# relais_platine_v2.net
KiCad netlist of a schematic drawn in EAGLE
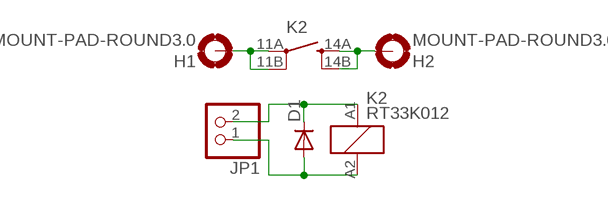
[diagram p0: schematic, sheet 1]

(export (version "E")
  (design (tool "Eeschema 10.0.6"))
  (components
    (comp (ref "D1")
      (value "DIODE-D-5")
      (footprint "eagle-import:D-5")
      (libsource (lib "eagle-import") (part "DIODE-D-5"))
    )
    (comp (ref "H1")
      (value "MOUNT-PAD-ROUND3.0")
      (footprint "eagle-import:3,0-PAD")
      (libsource (lib "eagle-import") (part "MOUNT-PAD-ROUND3.0"))
    )
    (comp (ref "H2")
      (value "MOUNT-PAD-ROUND3.0")
      (footprint "eagle-import:3,0-PAD")
      (libsource (lib "eagle-import") (part "MOUNT-PAD-ROUND3.0"))
    )
    (comp (ref "JP1")
      (value "PINHD-1X2")
      (footprint "eagle-import:1X02")
      (libsource (lib "eagle-import") (part "PINHD-1X2"))
    )
    (comp (ref "K2")
      (value "RT33K012")
      (footprint "eagle-import:RT-N_O16A5")
      (libsource (lib "eagle-import") (part "RT33K012"))
    )
  )
  (nets
    (net (code "1") (name "Net-(H1-MOUNT)") (class "Default")
      (node (ref "H1") (pin "B3,0") (pinfunction "MOUNT_B3,0") (pintype "passive"))
      (node (ref "K2") (pin "11A") (pinfunction "PA_11A") (pintype "passive"))
      (node (ref "K2") (pin "11B") (pinfunction "PB_11B") (pintype "passive"))
    )
    (net (code "2") (name "Net-(H2-MOUNT)") (class "Default")
      (node (ref "H2") (pin "B3,0") (pinfunction "MOUNT_B3,0") (pintype "passive"))
      (node (ref "K2") (pin "14A") (pinfunction "SA_14A") (pintype "passive"))
      (node (ref "K2") (pin "14B") (pinfunction "SB_14B") (pintype "passive"))
    )
    (net (code "3") (name "Net-(K2A-1)") (class "Default")
      (node (ref "D1") (pin "C") (pinfunction "C_C") (pintype "passive"))
      (node (ref "JP1") (pin "2") (pinfunction "2_2") (pintype "passive"))
      (node (ref "K2") (pin "A1") (pinfunction "1_A1") (pintype "passive"))
    )
    (net (code "4") (name "Net-(K2A-2)") (class "Default")
      (node (ref "D1") (pin "A") (pinfunction "A_A") (pintype "passive"))
      (node (ref "JP1") (pin "1") (pinfunction "1_1") (pintype "passive"))
      (node (ref "K2") (pin "A2") (pinfunction "2_A2") (pintype "passive"))
    )
  )
)
